# Interface_-_SWD.net
KiCad netlist of a schematic drawn in Altium Designer
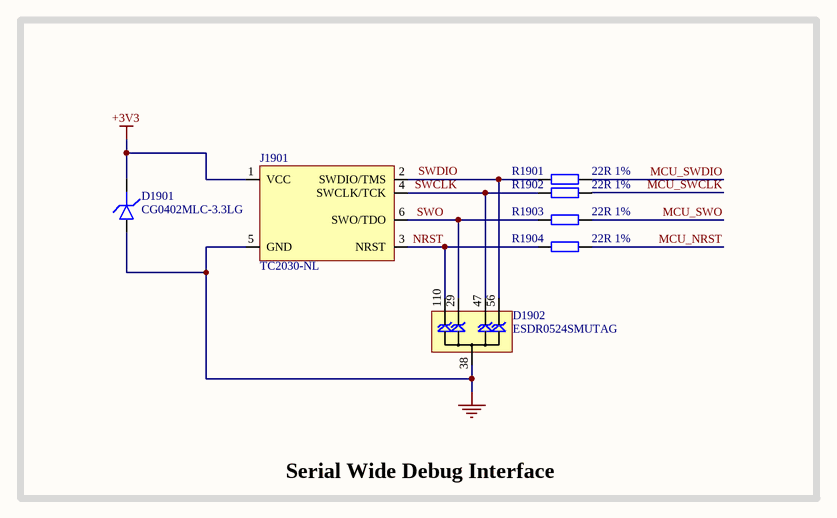
[diagram p0: Interface - SWD.SchDoc]

(export (version "E")
  (design (tool "Eeschema 10.0.6"))
  (components
    (comp (ref "D1901")
      (value "CG0402MLC-3.3LG")
      (footprint "D_0402")
      (description "Diode TVS / ESD 0402")
      (libsource (lib "Schematic-Lib-PhilsLab") (part "D_TVS_0402"))
    )
    (comp (ref "D1902")
      (value "ESDR0524SMUTAG")
      (footprint "uDFN-10-WIDE")
      (description "TVS Diode Array Low Capacitance ESD Protection 4-Channel (Vwork=5V, Vclamp=15V)")
      (fields (field (name "MANUFACTURER") "onsemi"))
      (libsource (lib "Schematic-Lib-PhilsLab") (part "ESDR0524SMUTAG"))
    )
    (comp (ref "J1901")
      (value "TC2030-NL")
      (footprint "TC2030-NL-FP")
      (description "Tag-Connect No-Solder SWD Debug Connector (No Legs) DO NOT PLACE")
      (fields
        (field (name "MANUFACTURER") "Tag-Connect")
        (field (name "MANUFACTURER PART NUMBER") "TC2030-NL-FP")
      )
      (libsource (lib "Schematic-Lib-PhilsLab") (part "TC2030-NL"))
    )
    (comp (ref "R1901")
      (value "22R 1%")
      (footprint "RES_0402")
      (description "Resistor SMD 0402")
      (fields
        (field (name "MANUFACTURER") "PANASONIC")
        (field (name "MANUFACTURER PART NUMBER") "ERJPA2F22R0X")
      )
      (libsource (lib "Schematic-Lib-PhilsLab") (part "RES_0402"))
    )
    (comp (ref "R1902")
      (value "22R 1%")
      (footprint "RES_0402")
      (description "Resistor SMD 0402")
      (fields
        (field (name "MANUFACTURER") "PANASONIC")
        (field (name "MANUFACTURER PART NUMBER") "ERJPA2F22R0X")
      )
      (libsource (lib "Schematic-Lib-PhilsLab") (part "RES_0402"))
    )
    (comp (ref "R1903")
      (value "22R 1%")
      (footprint "RES_0402")
      (description "Resistor SMD 0402")
      (fields
        (field (name "MANUFACTURER") "PANASONIC")
        (field (name "MANUFACTURER PART NUMBER") "ERJPA2F22R0X")
      )
      (libsource (lib "Schematic-Lib-PhilsLab") (part "RES_0402"))
    )
    (comp (ref "R1904")
      (value "22R 1%")
      (footprint "RES_0402")
      (description "Resistor SMD 0402")
      (fields
        (field (name "MANUFACTURER") "PANASONIC")
        (field (name "MANUFACTURER PART NUMBER") "ERJPA2F22R0X")
      )
      (libsource (lib "Schematic-Lib-PhilsLab") (part "RES_0402"))
    )
  )
  (nets
    (net (code "1") (name "+3V3") (class "Default")
      (node (ref "D1901") (pin "K") (pinfunction "K_K") (pintype "passive"))
      (node (ref "J1901") (pin "1") (pinfunction "VCC_1") (pintype "passive"))
    )
    (net (code "2") (name "/MCU_NRST") (class "Default")
      (node (ref "R1904") (pin "1") (pinfunction "1_1") (pintype "passive"))
    )
    (net (code "3") (name "/MCU_SWCLK") (class "Default")
      (node (ref "R1902") (pin "1") (pinfunction "1_1") (pintype "passive"))
    )
    (net (code "4") (name "/MCU_SWDIO") (class "Default")
      (node (ref "R1901") (pin "1") (pinfunction "1_1") (pintype "passive"))
    )
    (net (code "5") (name "/MCU_SWO") (class "Default")
      (node (ref "R1903") (pin "1") (pinfunction "1_1") (pintype "passive"))
    )
    (net (code "6") (name "/NRST") (class "Default")
      (node (ref "D1902") (pin "110") (pintype "passive"))
      (node (ref "J1901") (pin "3") (pinfunction "NRST_3") (pintype "passive"))
      (node (ref "R1904") (pin "2") (pinfunction "2_2") (pintype "passive"))
    )
    (net (code "9") (name "/SWCLK") (class "Default")
      (node (ref "D1902") (pin "47") (pintype "passive"))
      (node (ref "J1901") (pin "4") (pinfunction "SWCLK/TCK_4") (pintype "passive"))
      (node (ref "R1902") (pin "2") (pinfunction "2_2") (pintype "passive"))
    )
    (net (code "10") (name "/SWDIO") (class "Default")
      (node (ref "D1902") (pin "56") (pintype "passive"))
      (node (ref "J1901") (pin "2") (pinfunction "SWDIO/TMS_2") (pintype "passive"))
      (node (ref "R1901") (pin "2") (pinfunction "2_2") (pintype "passive"))
    )
    (net (code "11") (name "/SWO") (class "Default")
      (node (ref "D1902") (pin "29") (pintype "passive"))
      (node (ref "J1901") (pin "6") (pinfunction "SWO/TDO_6") (pintype "passive"))
      (node (ref "R1903") (pin "2") (pinfunction "2_2") (pintype "passive"))
    )
    (net (code "12") (name "GND") (class "Default")
      (node (ref "D1901") (pin "A") (pinfunction "A_A") (pintype "passive"))
      (node (ref "D1902") (pin "38") (pinfunction "GND_38") (pintype "passive"))
      (node (ref "J1901") (pin "5") (pinfunction "GND_5") (pintype "passive"))
    )
  )
)
